# BatteryPower.net
KiCad netlist of a schematic drawn in EAGLE
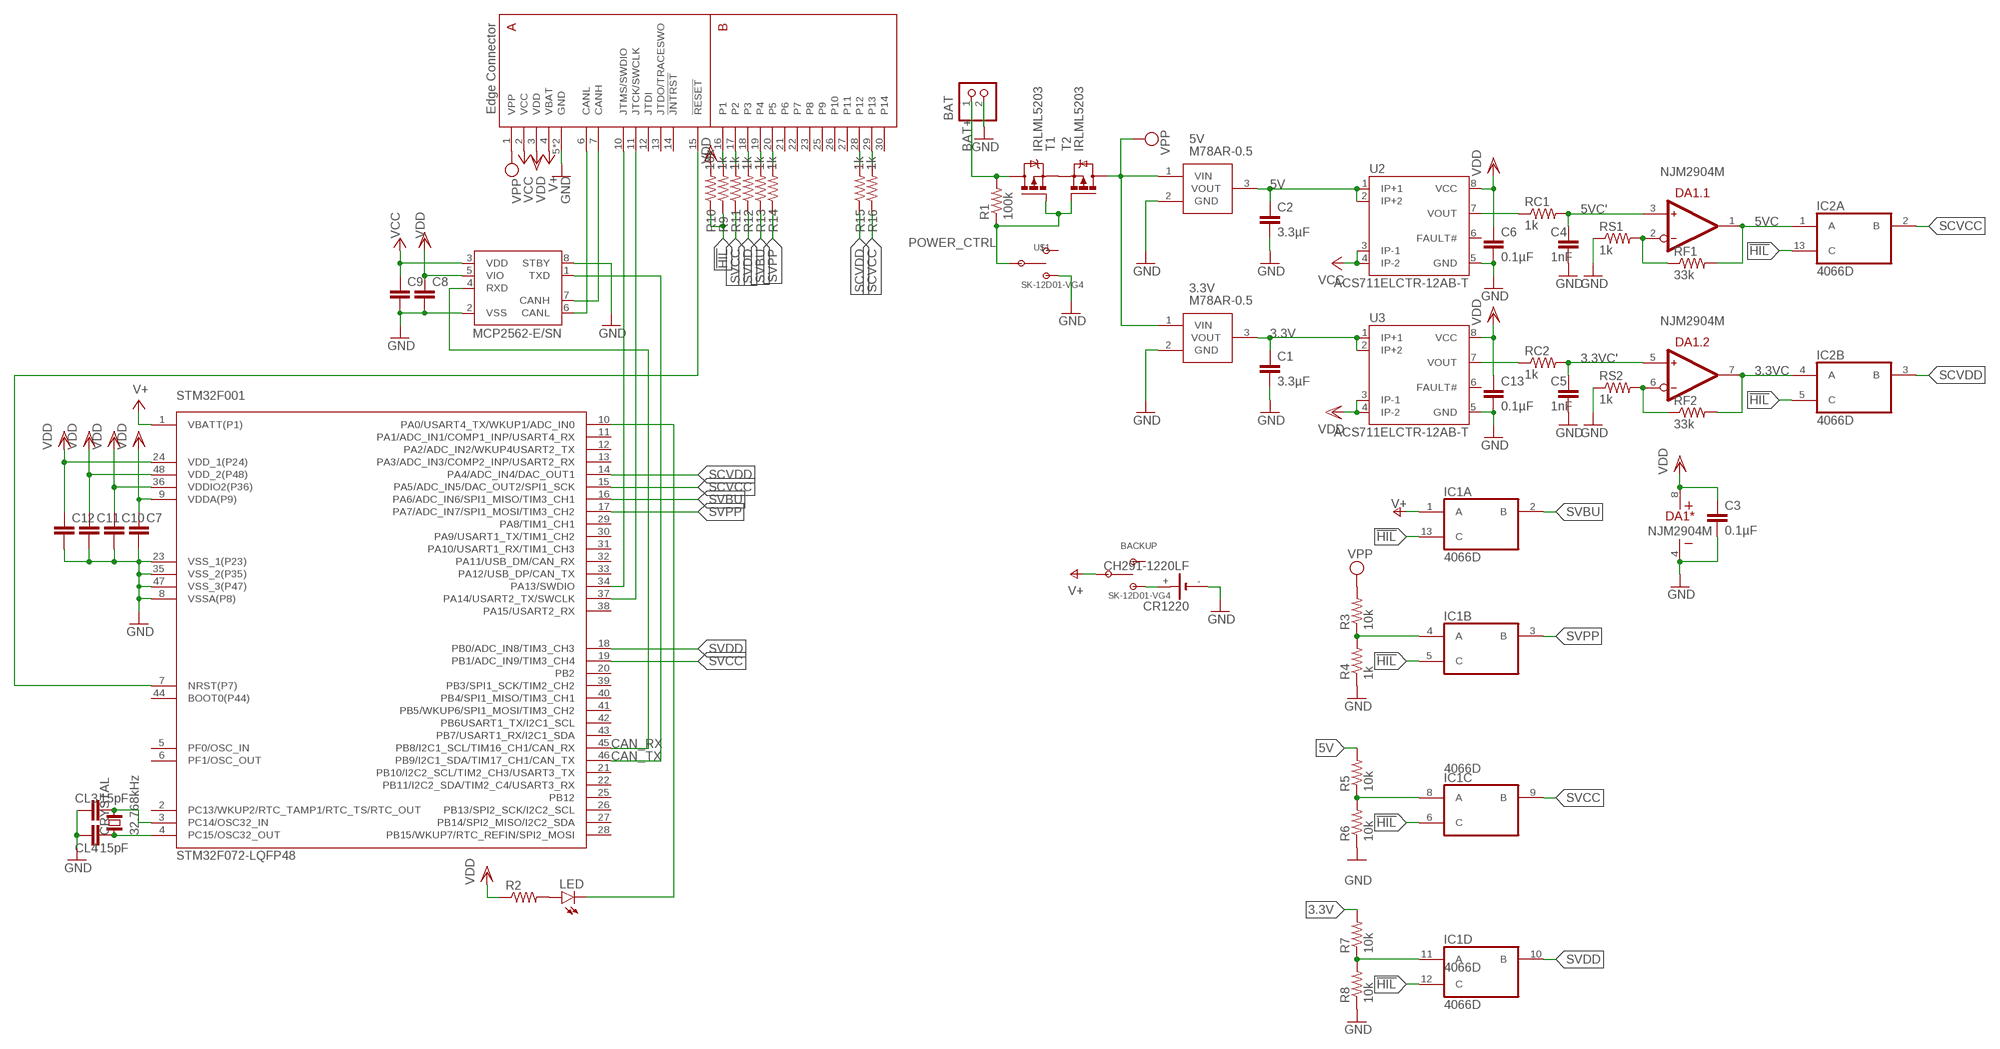
[diagram p0: schematic, sheet 1]

(export (version "E")
  (design (tool "Eeschema 10.0.6"))
  (components
    (comp (ref "3.3V")
      (value "M78AR-0.5")
      (footprint "eagle-import:SHDR3W75P0X254_1X3_1128X755X10")
      (libsource (lib "eagle-import") (part "M78AR-0.5"))
    )
    (comp (ref "5V")
      (value "M78AR-0.5")
      (footprint "eagle-import:SHDR3W75P0X254_1X3_1128X755X10")
      (libsource (lib "eagle-import") (part "M78AR-0.5"))
    )
    (comp (ref "BACKUP")
      (value "SK-12D01-VG4")
      (footprint "eagle-import:SK-12D01-VG4")
      (libsource (lib "eagle-import") (part "SK-12D01-VG4"))
    )
    (comp (ref "BAT")
      (value "S2B-XH-A")
      (footprint "eagle-import:S2B-XH-A")
      (libsource (lib "eagle-import") (part "S2B-XH-A"))
    )
    (comp (ref "C1")
      (value "3.3µF")
      (footprint "eagle-import:C0603K")
      (libsource (lib "eagle-import") (part "C-EUC0603K"))
    )
    (comp (ref "C2")
      (value "3.3µF")
      (footprint "eagle-import:C0603K")
      (libsource (lib "eagle-import") (part "C-EUC0603K"))
    )
    (comp (ref "C3")
      (value "0.1µF")
      (footprint "eagle-import:C0603K")
      (libsource (lib "eagle-import") (part "C-EUC0603K"))
    )
    (comp (ref "C4")
      (value "1nF")
      (footprint "eagle-import:C0603K")
      (libsource (lib "eagle-import") (part "C-EUC0603K"))
    )
    (comp (ref "C5")
      (value "1nF")
      (footprint "eagle-import:C0603K")
      (libsource (lib "eagle-import") (part "C-EUC0603K"))
    )
    (comp (ref "C6")
      (value "0.1µF")
      (footprint "eagle-import:C0603K")
      (libsource (lib "eagle-import") (part "C-EUC0603K"))
    )
    (comp (ref "C7")
      (value "C-EUC0603K")
      (footprint "eagle-import:C0603K")
      (libsource (lib "eagle-import") (part "C-EUC0603K"))
    )
    (comp (ref "C8")
      (value "C-EUC0603K")
      (footprint "eagle-import:C0603K")
      (libsource (lib "eagle-import") (part "C-EUC0603K"))
    )
    (comp (ref "C9")
      (value "C-EUC0603K")
      (footprint "eagle-import:C0603K")
      (libsource (lib "eagle-import") (part "C-EUC0603K"))
    )
    (comp (ref "C10")
      (value "C-EUC0603K")
      (footprint "eagle-import:C0603K")
      (libsource (lib "eagle-import") (part "C-EUC0603K"))
    )
    (comp (ref "C11")
      (value "C-EUC0603K")
      (footprint "eagle-import:C0603K")
      (libsource (lib "eagle-import") (part "C-EUC0603K"))
    )
    (comp (ref "C12")
      (value "C-EUC0603K")
      (footprint "eagle-import:C0603K")
      (libsource (lib "eagle-import") (part "C-EUC0603K"))
    )
    (comp (ref "C13")
      (value "0.1µF")
      (footprint "eagle-import:C0603K")
      (libsource (lib "eagle-import") (part "C-EUC0603K"))
    )
    (comp (ref "CL3")
      (value "15pF")
      (footprint "eagle-import:C0603K")
      (libsource (lib "eagle-import") (part "C-EUC0603K"))
    )
    (comp (ref "CL4")
      (value "15pF")
      (footprint "eagle-import:C0603K")
      (libsource (lib "eagle-import") (part "C-EUC0603K"))
    )
    (comp (ref "CR1220")
      (value "CH291-1220LF")
      (footprint "eagle-import:CH291-1220LF")
      (libsource (lib "eagle-import") (part "CH291-1220LF"))
    )
    (comp (ref "CRYSTAL")
      (value "32.768kHz")
      (footprint "eagle-import:FC-255")
      (libsource (lib "eagle-import") (part "CRYTALFC-255"))
    )
    (comp (ref "DA1")
      (value "NJM2904M")
      (footprint "eagle-import:SO-8")
      (libsource (lib "eagle-import") (part "NJM2904M"))
    )
    (comp (ref "IC1")
      (value "4066D")
      (footprint "eagle-import:SO14")
      (libsource (lib "eagle-import") (part "4066D"))
    )
    (comp (ref "IC2")
      (value "4066D")
      (footprint "eagle-import:SO14")
      (libsource (lib "eagle-import") (part "4066D"))
    )
    (comp (ref "LED")
      (value "LEDCHIP-LED0603")
      (footprint "eagle-import:CHIP-LED0603")
      (libsource (lib "eagle-import") (part "LEDCHIP-LED0603"))
    )
    (comp (ref "MCP2562")
      (value "MCP2562-E/SN")
      (footprint "eagle-import:SOIC127P600X175-8N")
      (fields (field (name "MF") "Microchip"))
      (libsource (lib "eagle-import") (part "MCP2562-E/SN"))
    )
    (comp (ref "R1")
      (value "100k")
      (footprint "eagle-import:R0603")
      (libsource (lib "eagle-import") (part "R-US_R0603"))
    )
    (comp (ref "R2")
      (value "R-US_R0603")
      (footprint "eagle-import:R0603")
      (libsource (lib "eagle-import") (part "R-US_R0603"))
    )
    (comp (ref "R3")
      (value "10k")
      (footprint "eagle-import:R0603")
      (libsource (lib "eagle-import") (part "R-US_R0603"))
    )
    (comp (ref "R4")
      (value "1k")
      (footprint "eagle-import:R0603")
      (libsource (lib "eagle-import") (part "R-US_R0603"))
    )
    (comp (ref "R5")
      (value "10k")
      (footprint "eagle-import:R0603")
      (libsource (lib "eagle-import") (part "R-US_R0603"))
    )
    (comp (ref "R6")
      (value "10k")
      (footprint "eagle-import:R0603")
      (libsource (lib "eagle-import") (part "R-US_R0603"))
    )
    (comp (ref "R7")
      (value "10k")
      (footprint "eagle-import:R0603")
      (libsource (lib "eagle-import") (part "R-US_R0603"))
    )
    (comp (ref "R8")
      (value "10k")
      (footprint "eagle-import:R0603")
      (libsource (lib "eagle-import") (part "R-US_R0603"))
    )
    (comp (ref "R9")
      (value "1k")
      (footprint "eagle-import:R0603")
      (libsource (lib "eagle-import") (part "R-US_R0603"))
    )
    (comp (ref "R10")
      (value "10k")
      (footprint "eagle-import:R0603")
      (libsource (lib "eagle-import") (part "R-US_R0603"))
    )
    (comp (ref "R11")
      (value "1k")
      (footprint "eagle-import:R0603")
      (libsource (lib "eagle-import") (part "R-US_R0603"))
    )
    (comp (ref "R12")
      (value "1k")
      (footprint "eagle-import:R0603")
      (libsource (lib "eagle-import") (part "R-US_R0603"))
    )
    (comp (ref "R13")
      (value "1k")
      (footprint "eagle-import:R0603")
      (libsource (lib "eagle-import") (part "R-US_R0603"))
    )
    (comp (ref "R14")
      (value "1k")
      (footprint "eagle-import:R0603")
      (libsource (lib "eagle-import") (part "R-US_R0603"))
    )
    (comp (ref "R15")
      (value "1k")
      (footprint "eagle-import:R0603")
      (libsource (lib "eagle-import") (part "resistor_348_R-US_R0603"))
    )
    (comp (ref "R16")
      (value "1k")
      (footprint "eagle-import:R0603")
      (libsource (lib "eagle-import") (part "resistor_348_R-US_R0603"))
    )
    (comp (ref "RC1")
      (value "1k")
      (footprint "eagle-import:R0603")
      (libsource (lib "eagle-import") (part "R-US_R0603"))
    )
    (comp (ref "RC2")
      (value "1k")
      (footprint "eagle-import:R0603")
      (libsource (lib "eagle-import") (part "R-US_R0603"))
    )
    (comp (ref "RF1")
      (value "33k")
      (footprint "eagle-import:R0603")
      (libsource (lib "eagle-import") (part "R-US_R0603"))
    )
    (comp (ref "RF2")
      (value "33k")
      (footprint "eagle-import:R0603")
      (libsource (lib "eagle-import") (part "R-US_R0603"))
    )
    (comp (ref "RS1")
      (value "1k")
      (footprint "eagle-import:R0603")
      (libsource (lib "eagle-import") (part "R-US_R0603"))
    )
    (comp (ref "RS2")
      (value "1k")
      (footprint "eagle-import:R0603")
      (libsource (lib "eagle-import") (part "R-US_R0603"))
    )
    (comp (ref "STM32F001")
      (value "STM32F072-LQFP48")
      (footprint "eagle-import:LQFP48")
      (libsource (lib "eagle-import") (part "STM32F072-LQFP48"))
    )
    (comp (ref "T1")
      (value "IRLML5203")
      (footprint "eagle-import:MICRO3")
      (libsource (lib "eagle-import") (part "IRLML5203"))
    )
    (comp (ref "T2")
      (value "IRLML5203")
      (footprint "eagle-import:MICRO3")
      (libsource (lib "eagle-import") (part "IRLML5203"))
    )
    (comp (ref "U$1")
      (value "SK-12D01-VG4")
      (footprint "eagle-import:SK-12D01-VG4")
      (libsource (lib "eagle-import") (part "SK-12D01-VG4"))
    )
    (comp (ref "U$2")
      (value "EDGE30")
      (footprint "eagle-import:EDGE30")
      (libsource (lib "eagle-import") (part "EDGE30"))
    )
    (comp (ref "U2")
      (value "ACS711ELCTR-12AB-T")
      (footprint "eagle-import:SOIC8")
      (libsource (lib "eagle-import") (part "ACS711ELC?TR-12AB-T"))
    )
    (comp (ref "U3")
      (value "ACS711ELCTR-12AB-T")
      (footprint "eagle-import:SOIC8")
      (libsource (lib "eagle-import") (part "ACS711ELC?TR-12AB-T"))
    )
  )
  (nets
    (net (code "1") (name "/3.3VC") (class "Default")
      (node (ref "DA1") (pin "7") (pinfunction "OUT_7") (pintype "output"))
      (node (ref "IC2") (pin "4") (pinfunction "A_4") (pintype "tri_state"))
      (node (ref "RF2") (pin "2") (pinfunction "2_2") (pintype "passive"))
    )
    (net (code "2") (name "/3.3VC'") (class "Default")
      (node (ref "C5") (pin "1") (pinfunction "1_1") (pintype "passive"))
      (node (ref "DA1") (pin "5") (pinfunction "IN+_5") (pintype "input"))
      (node (ref "RC2") (pin "2") (pinfunction "2_2") (pintype "passive"))
    )
    (net (code "3") (name "/5VC") (class "Default")
      (node (ref "DA1") (pin "1") (pinfunction "OUT_1") (pintype "output"))
      (node (ref "IC2") (pin "1") (pinfunction "A_1") (pintype "tri_state"))
      (node (ref "RF1") (pin "2") (pinfunction "2_2") (pintype "passive"))
    )
    (net (code "4") (name "/5VC'") (class "Default")
      (node (ref "C4") (pin "1") (pinfunction "1_1") (pintype "passive"))
      (node (ref "DA1") (pin "3") (pinfunction "IN+_3") (pintype "input"))
      (node (ref "RC1") (pin "2") (pinfunction "2_2") (pintype "passive"))
    )
    (net (code "5") (name "/BAT+") (class "Default")
      (node (ref "BAT") (pin "1") (pinfunction "1_1") (pintype "passive"))
      (node (ref "R1") (pin "2") (pinfunction "2_2") (pintype "passive"))
      (node (ref "T1") (pin "3") (pinfunction "D_3") (pintype "passive"))
    )
    (net (code "6") (name "/CAN_RX") (class "Default")
      (node (ref "MCP2562") (pin "4") (pinfunction "RXD_4") (pintype "output"))
      (node (ref "STM32F001") (pin "45") (pinfunction "PB8/I2C1_SCL/TIM16_CH1/CAN_RX_45") (pintype "bidirectional"))
    )
    (net (code "7") (name "/CAN_TX") (class "Default")
      (node (ref "MCP2562") (pin "1") (pinfunction "TXD_1") (pintype "input"))
      (node (ref "STM32F001") (pin "46") (pinfunction "PB9/I2C1_SDA/TIM17_CH1/CAN_TX_46") (pintype "bidirectional"))
    )
    (net (code "8") (name "/POWER_CTRL") (class "Default")
      (node (ref "R1") (pin "1") (pinfunction "1_1") (pintype "passive"))
      (node (ref "T1") (pin "1") (pinfunction "G_1") (pintype "passive"))
      (node (ref "T2") (pin "1") (pinfunction "G_1") (pintype "passive"))
      (node (ref "U$1") (pin "C") (pinfunction "C_C") (pintype "bidirectional"))
    )
    (net (code "9") (name "/~{HIL}") (class "Default")
      (node (ref "IC1") (pin "12") (pinfunction "C_12") (pintype "input"))
      (node (ref "IC1") (pin "13") (pinfunction "C_13") (pintype "input"))
      (node (ref "IC1") (pin "5") (pinfunction "C_5") (pintype "input"))
      (node (ref "IC1") (pin "6") (pinfunction "C_6") (pintype "input"))
      (node (ref "IC2") (pin "13") (pinfunction "C_13") (pintype "input"))
      (node (ref "IC2") (pin "5") (pinfunction "C_5") (pintype "input"))
      (node (ref "R10") (pin "1") (pinfunction "1_1") (pintype "passive"))
      (node (ref "R9") (pin "1") (pinfunction "1_1") (pintype "passive"))
    )
    (net (code "10") (name "3.3V") (class "Default")
      (node (ref "3.3V") (pin "3") (pinfunction "VOUT_3") (pintype "power_in"))
      (node (ref "C1") (pin "1") (pinfunction "1_1") (pintype "passive"))
      (node (ref "R7") (pin "2") (pinfunction "2_2") (pintype "passive"))
      (node (ref "U3") (pin "1") (pinfunction "IP+1_1") (pintype "bidirectional"))
      (node (ref "U3") (pin "2") (pinfunction "IP+2_2") (pintype "bidirectional"))
    )
    (net (code "11") (name "5V") (class "Default")
      (node (ref "5V") (pin "3") (pinfunction "VOUT_3") (pintype "power_in"))
      (node (ref "C2") (pin "1") (pinfunction "1_1") (pintype "passive"))
      (node (ref "R5") (pin "2") (pinfunction "2_2") (pintype "passive"))
      (node (ref "U2") (pin "1") (pinfunction "IP+1_1") (pintype "bidirectional"))
      (node (ref "U2") (pin "2") (pinfunction "IP+2_2") (pintype "bidirectional"))
    )
    (net (code "12") (name "GND") (class "Default")
      (node (ref "3.3V") (pin "2") (pinfunction "GND_2") (pintype "power_in"))
      (node (ref "5V") (pin "2") (pinfunction "GND_2") (pintype "power_in"))
      (node (ref "BAT") (pin "2") (pinfunction "2_2") (pintype "passive"))
      (node (ref "C1") (pin "2") (pinfunction "2_2") (pintype "passive"))
      (node (ref "C10") (pin "2") (pinfunction "2_2") (pintype "passive"))
      (node (ref "C11") (pin "2") (pinfunction "2_2") (pintype "passive"))
      (node (ref "C12") (pin "2") (pinfunction "2_2") (pintype "passive"))
      (node (ref "C13") (pin "2") (pinfunction "2_2") (pintype "passive"))
      (node (ref "C2") (pin "2") (pinfunction "2_2") (pintype "passive"))
      (node (ref "C3") (pin "2") (pinfunction "2_2") (pintype "passive"))
      (node (ref "C4") (pin "2") (pinfunction "2_2") (pintype "passive"))
      (node (ref "C5") (pin "2") (pinfunction "2_2") (pintype "passive"))
      (node (ref "C6") (pin "2") (pinfunction "2_2") (pintype "passive"))
      (node (ref "C7") (pin "2") (pinfunction "2_2") (pintype "passive"))
      (node (ref "C8") (pin "2") (pinfunction "2_2") (pintype "passive"))
      (node (ref "C9") (pin "2") (pinfunction "2_2") (pintype "passive"))
      (node (ref "CL3") (pin "1") (pinfunction "1_1") (pintype "passive"))
      (node (ref "CL4") (pin "1") (pinfunction "1_1") (pintype "passive"))
      (node (ref "CR1220") (pin "-") (pinfunction "-_-") (pintype "passive"))
      (node (ref "DA1") (pin "4") (pinfunction "V-_4") (pintype "power_in"))
      (node (ref "MCP2562") (pin "2") (pinfunction "VSS_2") (pintype "power_in"))
      (node (ref "MCP2562") (pin "8") (pinfunction "STBY_8") (pintype "input"))
      (node (ref "R4") (pin "1") (pinfunction "1_1") (pintype "passive"))
      (node (ref "R6") (pin "1") (pinfunction "1_1") (pintype "passive"))
      (node (ref "R8") (pin "1") (pinfunction "1_1") (pintype "passive"))
      (node (ref "RS1") (pin "1") (pinfunction "1_1") (pintype "passive"))
      (node (ref "RS2") (pin "1") (pinfunction "1_1") (pintype "passive"))
      (node (ref "STM32F001") (pin "23") (pinfunction "VSS_1(P23)_23") (pintype "bidirectional"))
      (node (ref "STM32F001") (pin "35") (pinfunction "VSS_2(P35)_35") (pintype "bidirectional"))
      (node (ref "STM32F001") (pin "47") (pinfunction "VSS_3(P47)_47") (pintype "bidirectional"))
      (node (ref "STM32F001") (pin "8") (pinfunction "VSSA(P8)_8") (pintype "bidirectional"))
      (node (ref "U$1") (pin "B") (pinfunction "B_B") (pintype "bidirectional"))
      (node (ref "U$2") (pin "5") (pinfunction "GND_5") (pintype "power_in"))
      (node (ref "U$2") (pin "8") (pinfunction "GND_8") (pintype "power_in"))
      (node (ref "U2") (pin "5") (pinfunction "GND_5") (pintype "bidirectional"))
      (node (ref "U3") (pin "5") (pinfunction "GND_5") (pintype "bidirectional"))
    )
    (net (code "13") (name "Net-(BACKUP-PadB)") (class "Default")
      (node (ref "BACKUP") (pin "B") (pinfunction "B_B") (pintype "bidirectional"))
      (node (ref "CR1220") (pin "+") (pinfunction "+_+") (pintype "passive"))
    )
    (net (code "14") (name "Net-(DA1B-IN-)") (class "Default")
      (node (ref "DA1") (pin "2") (pinfunction "IN-_2") (pintype "input"))
      (node (ref "RF1") (pin "1") (pinfunction "1_1") (pintype "passive"))
      (node (ref "RS1") (pin "2") (pinfunction "2_2") (pintype "passive"))
    )
    (net (code "15") (name "Net-(DA1C-IN-)") (class "Default")
      (node (ref "DA1") (pin "6") (pinfunction "IN-_6") (pintype "input"))
      (node (ref "RF2") (pin "1") (pinfunction "1_1") (pintype "passive"))
      (node (ref "RS2") (pin "2") (pinfunction "2_2") (pintype "passive"))
    )
    (net (code "16") (name "Net-(IC1B-A)") (class "Default")
      (node (ref "IC1") (pin "4") (pinfunction "A_4") (pintype "tri_state"))
      (node (ref "R3") (pin "1") (pinfunction "1_1") (pintype "passive"))
      (node (ref "R4") (pin "2") (pinfunction "2_2") (pintype "passive"))
    )
    (net (code "17") (name "Net-(IC1C-A)") (class "Default")
      (node (ref "IC1") (pin "8") (pinfunction "A_8") (pintype "tri_state"))
      (node (ref "R5") (pin "1") (pinfunction "1_1") (pintype "passive"))
      (node (ref "R6") (pin "2") (pinfunction "2_2") (pintype "passive"))
    )
    (net (code "18") (name "Net-(IC1D-A)") (class "Default")
      (node (ref "IC1") (pin "11") (pinfunction "A_11") (pintype "tri_state"))
      (node (ref "R7") (pin "1") (pinfunction "1_1") (pintype "passive"))
      (node (ref "R8") (pin "2") (pinfunction "2_2") (pintype "passive"))
    )
    (net (code "19") (name "Net-(LED-PadA)") (class "Default")
      (node (ref "LED") (pin "A") (pinfunction "A_A") (pintype "passive"))
      (node (ref "R2") (pin "2") (pinfunction "2_2") (pintype "passive"))
    )
    (net (code "20") (name "Net-(MCP2562-CANH)") (class "Default")
      (node (ref "MCP2562") (pin "7") (pinfunction "CANH_7") (pintype "input"))
      (node (ref "U$2") (pin "7") (pinfunction "CANH_7") (pintype "bidirectional"))
    )
    (net (code "21") (name "Net-(MCP2562-CANL)") (class "Default")
      (node (ref "MCP2562") (pin "6") (pinfunction "CANL_6") (pintype "input"))
      (node (ref "U$2") (pin "6") (pinfunction "CANL_6") (pintype "bidirectional"))
    )
    (net (code "22") (name "Net-(STM32F001-NRST(P7))") (class "Default")
      (node (ref "STM32F001") (pin "7") (pinfunction "NRST(P7)_7") (pintype "bidirectional"))
      (node (ref "U$2") (pin "15") (pinfunction "~{RESET}_15") (pintype "bidirectional"))
    )
    (net (code "23") (name "Net-(STM32F001-PA0{slash}USART4_TX{slash}WKUP1{slash}ADC_IN0)") (class "Default")
      (node (ref "LED") (pin "C") (pinfunction "C_C") (pintype "passive"))
      (node (ref "STM32F001") (pin "10") (pinfunction "PA0/USART4_TX/WKUP1/ADC_IN0_10") (pintype "bidirectional"))
    )
    (net (code "24") (name "Net-(STM32F001-PA13{slash}SWDIO)") (class "Default")
      (node (ref "STM32F001") (pin "34") (pinfunction "PA13/SWDIO_34") (pintype "bidirectional"))
      (node (ref "U$2") (pin "10") (pinfunction "JTMS/SWDIO_10") (pintype "bidirectional"))
    )
    (net (code "25") (name "Net-(STM32F001-PA14{slash}USART2_TX{slash}SWCLK)") (class "Default")
      (node (ref "STM32F001") (pin "37") (pinfunction "PA14/USART2_TX/SWCLK_37") (pintype "bidirectional"))
      (node (ref "U$2") (pin "11") (pinfunction "JTCK/SWCLK_11") (pintype "bidirectional"))
    )
    (net (code "26") (name "Net-(STM32F001-PC14{slash}OSC32_IN)") (class "Default")
      (node (ref "CL3") (pin "2") (pinfunction "2_2") (pintype "passive"))
      (node (ref "CRYSTAL") (pin "2") (pinfunction "2_2") (pintype "passive"))
      (node (ref "STM32F001") (pin "3") (pinfunction "PC14/OSC32_IN_3") (pintype "bidirectional"))
    )
    (net (code "27") (name "Net-(STM32F001-PC15{slash}OSC32_OUT)") (class "Default")
      (node (ref "CL4") (pin "2") (pinfunction "2_2") (pintype "passive"))
      (node (ref "CRYSTAL") (pin "1") (pinfunction "1_1") (pintype "passive"))
      (node (ref "STM32F001") (pin "4") (pinfunction "PC15/OSC32_OUT_4") (pintype "bidirectional"))
    )
    (net (code "28") (name "Net-(T1-S)") (class "Default")
      (node (ref "T1") (pin "2") (pinfunction "S_2") (pintype "passive"))
      (node (ref "T2") (pin "2") (pinfunction "S_2") (pintype "passive"))
    )
    (net (code "29") (name "Net-(U$2-P1)") (class "Default")
      (node (ref "R9") (pin "2") (pinfunction "2_2") (pintype "passive"))
      (node (ref "U$2") (pin "16") (pinfunction "P1_16") (pintype "bidirectional"))
    )
    (net (code "30") (name "Net-(U$2-P2)") (class "Default")
      (node (ref "R11") (pin "2") (pinfunction "2_2") (pintype "passive"))
      (node (ref "U$2") (pin "17") (pinfunction "P2_17") (pintype "bidirectional"))
    )
    (net (code "31") (name "Net-(U$2-P3)") (class "Default")
      (node (ref "R12") (pin "2") (pinfunction "2_2") (pintype "passive"))
      (node (ref "U$2") (pin "18") (pinfunction "P3_18") (pintype "bidirectional"))
    )
    (net (code "32") (name "Net-(U$2-P4)") (class "Default")
      (node (ref "R13") (pin "2") (pinfunction "2_2") (pintype "passive"))
      (node (ref "U$2") (pin "19") (pinfunction "P4_19") (pintype "bidirectional"))
    )
    (net (code "33") (name "Net-(U$2-P5)") (class "Default")
      (node (ref "R14") (pin "2") (pinfunction "2_2") (pintype "passive"))
      (node (ref "U$2") (pin "20") (pinfunction "P5_20") (pintype "bidirectional"))
    )
    (net (code "34") (name "Net-(U$2-P12)") (class "Default")
      (node (ref "R15") (pin "2") (pinfunction "2_2") (pintype "passive"))
      (node (ref "U$2") (pin "28") (pinfunction "P12_28") (pintype "bidirectional"))
    )
    (net (code "35") (name "Net-(U$2-P13)") (class "Default")
      (node (ref "R16") (pin "2") (pinfunction "2_2") (pintype "passive"))
      (node (ref "U$2") (pin "29") (pinfunction "P13_29") (pintype "bidirectional"))
    )
    (net (code "36") (name "Net-(U2-VOUT)") (class "Default")
      (node (ref "RC1") (pin "1") (pinfunction "1_1") (pintype "passive"))
      (node (ref "U2") (pin "7") (pinfunction "VOUT_7") (pintype "bidirectional"))
    )
    (net (code "37") (name "Net-(U3-VOUT)") (class "Default")
      (node (ref "RC2") (pin "1") (pinfunction "1_1") (pintype "passive"))
      (node (ref "U3") (pin "7") (pinfunction "VOUT_7") (pintype "bidirectional"))
    )
    (net (code "38") (name "SCVCC") (class "Default")
      (node (ref "IC2") (pin "2") (pinfunction "B_2") (pintype "tri_state"))
      (node (ref "R16") (pin "1") (pinfunction "1_1") (pintype "passive"))
      (node (ref "STM32F001") (pin "15") (pinfunction "PA5/ADC_IN5/DAC_OUT2/SPI1_SCK_15") (pintype "bidirectional"))
    )
    (net (code "39") (name "SCVDD") (class "Default")
      (node (ref "IC2") (pin "3") (pinfunction "B_3") (pintype "tri_state"))
      (node (ref "R15") (pin "1") (pinfunction "1_1") (pintype "passive"))
      (node (ref "STM32F001") (pin "14") (pinfunction "PA4/ADC_IN4/DAC_OUT1_14") (pintype "bidirectional"))
    )
    (net (code "40") (name "SVBU") (class "Default")
      (node (ref "IC1") (pin "2") (pinfunction "B_2") (pintype "tri_state"))
      (node (ref "R13") (pin "1") (pinfunction "1_1") (pintype "passive"))
      (node (ref "STM32F001") (pin "16") (pinfunction "PA6/ADC_IN6/SPI1_MISO/TIM3_CH1_16") (pintype "bidirectional"))
    )
    (net (code "41") (name "SVCC") (class "Default")
      (node (ref "IC1") (pin "9") (pinfunction "B_9") (pintype "tri_state"))
      (node (ref "R11") (pin "1") (pinfunction "1_1") (pintype "passive"))
      (node (ref "STM32F001") (pin "19") (pinfunction "PB1/ADC_IN9/TIM3_CH4_19") (pintype "bidirectional"))
    )
    (net (code "42") (name "SVDD") (class "Default")
      (node (ref "IC1") (pin "10") (pinfunction "B_10") (pintype "tri_state"))
      (node (ref "R12") (pin "1") (pinfunction "1_1") (pintype "passive"))
      (node (ref "STM32F001") (pin "18") (pinfunction "PB0/ADC_IN8/TIM3_CH3_18") (pintype "bidirectional"))
    )
    (net (code "43") (name "SVPP") (class "Default")
      (node (ref "IC1") (pin "3") (pinfunction "B_3") (pintype "tri_state"))
      (node (ref "R14") (pin "1") (pinfunction "1_1") (pintype "passive"))
      (node (ref "STM32F001") (pin "17") (pinfunction "PA7/ADC_IN7/SPI1_MOSI/TIM3_CH2_17") (pintype "bidirectional"))
    )
    (net (code "44") (name "V+") (class "Default")
      (node (ref "BACKUP") (pin "C") (pinfunction "C_C") (pintype "bidirectional"))
      (node (ref "IC1") (pin "1") (pinfunction "A_1") (pintype "tri_state"))
      (node (ref "STM32F001") (pin "1") (pinfunction "VBATT(P1)_1") (pintype "bidirectional"))
      (node (ref "U$2") (pin "4") (pinfunction "VBAT_4") (pintype "power_in"))
    )
    (net (code "45") (name "VCC") (class "Default")
      (node (ref "C9") (pin "1") (pinfunction "1_1") (pintype "passive"))
      (node (ref "MCP2562") (pin "3") (pinfunction "VDD_3") (pintype "power_in"))
      (node (ref "U$2") (pin "2") (pinfunction "VCC_2") (pintype "power_in"))
      (node (ref "U2") (pin "3") (pinfunction "IP-1_3") (pintype "bidirectional"))
      (node (ref "U2") (pin "4") (pinfunction "IP-2_4") (pintype "bidirectional"))
    )
    (net (code "46") (name "VDD") (class "Default")
      (node (ref "C10") (pin "1") (pinfunction "1_1") (pintype "passive"))
      (node (ref "C11") (pin "1") (pinfunction "1_1") (pintype "passive"))
      (node (ref "C12") (pin "1") (pinfunction "1_1") (pintype "passive"))
      (node (ref "C13") (pin "1") (pinfunction "1_1") (pintype "passive"))
      (node (ref "C3") (pin "1") (pinfunction "1_1") (pintype "passive"))
      (node (ref "C6") (pin "1") (pinfunction "1_1") (pintype "passive"))
      (node (ref "C7") (pin "1") (pinfunction "1_1") (pintype "passive"))
      (node (ref "C8") (pin "1") (pinfunction "1_1") (pintype "passive"))
      (node (ref "DA1") (pin "8") (pinfunction "V+_8") (pintype "power_in"))
      (node (ref "MCP2562") (pin "5") (pinfunction "VIO_5") (pintype "power_in"))
      (node (ref "R10") (pin "2") (pinfunction "2_2") (pintype "passive"))
      (node (ref "R2") (pin "1") (pinfunction "1_1") (pintype "passive"))
      (node (ref "STM32F001") (pin "24") (pinfunction "VDD_1(P24)_24") (pintype "bidirectional"))
      (node (ref "STM32F001") (pin "36") (pinfunction "VDDIO2(P36)_36") (pintype "bidirectional"))
      (node (ref "STM32F001") (pin "48") (pinfunction "VDD_2(P48)_48") (pintype "bidirectional"))
      (node (ref "STM32F001") (pin "9") (pinfunction "VDDA(P9)_9") (pintype "bidirectional"))
      (node (ref "U$2") (pin "3") (pinfunction "VDD_3") (pintype "power_in"))
      (node (ref "U2") (pin "8") (pinfunction "VCC_8") (pintype "bidirectional"))
      (node (ref "U3") (pin "3") (pinfunction "IP-1_3") (pintype "bidirectional"))
      (node (ref "U3") (pin "4") (pinfunction "IP-2_4") (pintype "bidirectional"))
      (node (ref "U3") (pin "8") (pinfunction "VCC_8") (pintype "bidirectional"))
    )
    (net (code "47") (name "VPP") (class "Default")
      (node (ref "3.3V") (pin "1") (pinfunction "VIN_1") (pintype "power_in"))
      (node (ref "5V") (pin "1") (pinfunction "VIN_1") (pintype "power_in"))
      (node (ref "R3") (pin "2") (pinfunction "2_2") (pintype "passive"))
      (node (ref "T2") (pin "3") (pinfunction "D_3") (pintype "passive"))
      (node (ref "U$2") (pin "1") (pinfunction "VPP_1") (pintype "power_in"))
    )
    (net (code "48") (name "unconnected-(BACKUP-PadA)") (class "Default")
      (node (ref "BACKUP") (pin "A") (pinfunction "A_A") (pintype "bidirectional"))
    )
    (net (code "49") (name "unconnected-(STM32F001-BOOT0(P44)-Pad44)") (class "Default")
      (node (ref "STM32F001") (pin "44") (pinfunction "BOOT0(P44)_44") (pintype "bidirectional"))
    )
    (net (code "50") (name "unconnected-(STM32F001-PA1{slash}ADC_IN1{slash}COMP1_INP{slash}USART4_RX-Pad11)") (class "Default")
      (node (ref "STM32F001") (pin "11") (pinfunction "PA1/ADC_IN1/COMP1_INP/USART4_RX_11") (pintype "bidirectional"))
    )
    (net (code "51") (name "unconnected-(STM32F001-PA2{slash}ADC_IN2{slash}WKUP4USART2_TX-Pad12)") (class "Default")
      (node (ref "STM32F001") (pin "12") (pinfunction "PA2/ADC_IN2/WKUP4USART2_TX_12") (pintype "bidirectional"))
    )
    (net (code "52") (name "unconnected-(STM32F001-PA3{slash}ADC_IN3{slash}COMP2_INP{slash}USART2_RX-Pad13)") (class "Default")
      (node (ref "STM32F001") (pin "13") (pinfunction "PA3/ADC_IN3/COMP2_INP/USART2_RX_13") (pintype "bidirectional"))
    )
    (net (code "53") (name "unconnected-(STM32F001-PA8{slash}TIM1_CH1-Pad29)") (class "Default")
      (node (ref "STM32F001") (pin "29") (pinfunction "PA8/TIM1_CH1_29") (pintype "bidirectional"))
    )
    (net (code "54") (name "unconnected-(STM32F001-PA9{slash}USART1_TX{slash}TIM1_CH2-Pad30)") (class "Default")
      (node (ref "STM32F001") (pin "30") (pinfunction "PA9/USART1_TX/TIM1_CH2_30") (pintype "bidirectional"))
    )
    (net (code "55") (name "unconnected-(STM32F001-PA10{slash}USART1_RX{slash}TIM1_CH3-Pad31)") (class "Default")
      (node (ref "STM32F001") (pin "31") (pinfunction "PA10/USART1_RX/TIM1_CH3_31") (pintype "bidirectional"))
    )
    (net (code "56") (name "unconnected-(STM32F001-PA11{slash}USB_DM{slash}CAN_RX-Pad32)") (class "Default")
      (node (ref "STM32F001") (pin "32") (pinfunction "PA11/USB_DM/CAN_RX_32") (pintype "bidirectional"))
    )
    (net (code "57") (name "unconnected-(STM32F001-PA12{slash}USB_DP{slash}CAN_TX-Pad33)") (class "Default")
      (node (ref "STM32F001") (pin "33") (pinfunction "PA12/USB_DP/CAN_TX_33") (pintype "bidirectional"))
    )
    (net (code "58") (name "unconnected-(STM32F001-PA15{slash}USART2_RX-Pad38)") (class "Default")
      (node (ref "STM32F001") (pin "38") (pinfunction "PA15/USART2_RX_38") (pintype "bidirectional"))
    )
    (net (code "59") (name "unconnected-(STM32F001-PB2-Pad20)") (class "Default")
      (node (ref "STM32F001") (pin "20") (pinfunction "PB2_20") (pintype "bidirectional"))
    )
    (net (code "60") (name "unconnected-(STM32F001-PB3{slash}SPI1_SCK{slash}TIM2_CH2-Pad39)") (class "Default")
      (node (ref "STM32F001") (pin "39") (pinfunction "PB3/SPI1_SCK/TIM2_CH2_39") (pintype "bidirectional"))
    )
    (net (code "61") (name "unconnected-(STM32F001-PB4{slash}SPI1_MISO{slash}TIM3_CH1-Pad40)") (class "Default")
      (node (ref "STM32F001") (pin "40") (pinfunction "PB4/SPI1_MISO/TIM3_CH1_40") (pintype "bidirectional"))
    )
    (net (code "62") (name "unconnected-(STM32F001-PB5{slash}WKUP6{slash}SPI1_MOSI{slash}TIM3_CH2-Pad41)") (class "Default")
      (node (ref "STM32F001") (pin "41") (pinfunction "PB5/WKUP6/SPI1_MOSI/TIM3_CH2_41") (pintype "bidirectional"))
    )
    (net (code "63") (name "unconnected-(STM32F001-PB6USART1_TX{slash}I2C1_SCL-Pad42)") (class "Default")
      (node (ref "STM32F001") (pin "42") (pinfunction "PB6USART1_TX/I2C1_SCL_42") (pintype "bidirectional"))
    )
    (net (code "64") (name "unconnected-(STM32F001-PB7{slash}USART1_RX{slash}I2C1_SDA-Pad43)") (class "Default")
      (node (ref "STM32F001") (pin "43") (pinfunction "PB7/USART1_RX/I2C1_SDA_43") (pintype "bidirectional"))
    )
    (net (code "65") (name "unconnected-(STM32F001-PB10{slash}I2C2_SCL{slash}TIM2_CH3{slash}USART3_TX-Pad21)") (class "Default")
      (node (ref "STM32F001") (pin "21") (pinfunction "PB10/I2C2_SCL/TIM2_CH3/USART3_TX_21") (pintype "bidirectional"))
    )
    (net (code "66") (name "unconnected-(STM32F001-PB11{slash}I2C2_SDA{slash}TIM2_C4{slash}USART3_RX-Pad22)") (class "Default")
      (node (ref "STM32F001") (pin "22") (pinfunction "PB11/I2C2_SDA/TIM2_C4/USART3_RX_22") (pintype "bidirectional"))
    )
    (net (code "67") (name "unconnected-(STM32F001-PB12-Pad25)") (class "Default")
      (node (ref "STM32F001") (pin "25") (pinfunction "PB12_25") (pintype "bidirectional"))
    )
    (net (code "68") (name "unconnected-(STM32F001-PB13{slash}SPI2_SCK{slash}I2C2_SCL-Pad26)") (class "Default")
      (node (ref "STM32F001") (pin "26") (pinfunction "PB13/SPI2_SCK/I2C2_SCL_26") (pintype "bidirectional"))
    )
    (net (code "69") (name "unconnected-(STM32F001-PB14{slash}SPI2_MISO{slash}I2C2_SDA-Pad27)") (class "Default")
      (node (ref "STM32F001") (pin "27") (pinfunction "PB14/SPI2_MISO/I2C2_SDA_27") (pintype "bidirectional"))
    )
    (net (code "70") (name "unconnected-(STM32F001-PB15{slash}WKUP7{slash}RTC_REFIN{slash}SPI2_MOSI-Pad28)") (class "Default")
      (node (ref "STM32F001") (pin "28") (pinfunction "PB15/WKUP7/RTC_REFIN/SPI2_MOSI_28") (pintype "bidirectional"))
    )
    (net (code "71") (name "unconnected-(STM32F001-PC13{slash}WKUP2{slash}RTC_TAMP1{slash}RTC_TS{slash}RTC_OUT-Pad2)") (class "Default")
      (node (ref "STM32F001") (pin "2") (pinfunction "PC13/WKUP2/RTC_TAMP1/RTC_TS/RTC_OUT_2") (pintype "bidirectional"))
    )
    (net (code "72") (name "unconnected-(STM32F001-PF0{slash}OSC_IN-Pad5)") (class "Default")
      (node (ref "STM32F001") (pin "5") (pinfunction "PF0/OSC_IN_5") (pintype "bidirectional"))
    )
    (net (code "73") (name "unconnected-(STM32F001-PF1{slash}OSC_OUT-Pad6)") (class "Default")
      (node (ref "STM32F001") (pin "6") (pinfunction "PF1/OSC_OUT_6") (pintype "bidirectional"))
    )
    (net (code "74") (name "unconnected-(U$1-PadA)") (class "Default")
      (node (ref "U$1") (pin "A") (pinfunction "A_A") (pintype "bidirectional"))
    )
    (net (code "75") (name "unconnected-(U$2-JTDI-Pad12)") (class "Default")
      (node (ref "U$2") (pin "12") (pinfunction "JTDI_12") (pintype "bidirectional"))
    )
    (net (code "76") (name "unconnected-(U$2-JTDO{slash}TRACESWO-Pad13)") (class "Default")
      (node (ref "U$2") (pin "13") (pinfunction "JTDO/TRACESWO_13") (pintype "bidirectional"))
    )
    (net (code "77") (name "unconnected-(U$2-P6-Pad21)") (class "Default")
      (node (ref "U$2") (pin "21") (pinfunction "P6_21") (pintype "bidirectional"))
    )
    (net (code "78") (name "unconnected-(U$2-P7-Pad22)") (class "Default")
      (node (ref "U$2") (pin "22") (pinfunction "P7_22") (pintype "bidirectional"))
    )
    (net (code "79") (name "unconnected-(U$2-P8-Pad23)") (class "Default")
      (node (ref "U$2") (pin "23") (pinfunction "P8_23") (pintype "bidirectional"))
    )
    (net (code "80") (name "unconnected-(U$2-P9-Pad25)") (class "Default")
      (node (ref "U$2") (pin "25") (pinfunction "P9_25") (pintype "bidirectional"))
    )
    (net (code "81") (name "unconnected-(U$2-P10-Pad26)") (class "Default")
      (node (ref "U$2") (pin "26") (pinfunction "P10_26") (pintype "bidirectional"))
    )
    (net (code "82") (name "unconnected-(U$2-P11-Pad27)") (class "Default")
      (node (ref "U$2") (pin "27") (pinfunction "P11_27") (pintype "bidirectional"))
    )
    (net (code "83") (name "unconnected-(U$2-P14-Pad30)") (class "Default")
      (node (ref "U$2") (pin "30") (pinfunction "P14_30") (pintype "bidirectional"))
    )
    (net (code "84") (name "unconnected-(U$2-~{JNTRST}-Pad14)") (class "Default")
      (node (ref "U$2") (pin "14") (pinfunction "~{JNTRST}_14") (pintype "bidirectional"))
    )
    (net (code "85") (name "unconnected-(U2-FAULT#-Pad6)") (class "Default")
      (node (ref "U2") (pin "6") (pinfunction "FAULT#_6") (pintype "bidirectional"))
    )
    (net (code "86") (name "unconnected-(U3-FAULT#-Pad6)") (class "Default")
      (node (ref "U3") (pin "6") (pinfunction "FAULT#_6") (pintype "bidirectional"))
    )
  )
)
